# TLC5940Driver.net
KiCad netlist of a schematic drawn in EAGLE
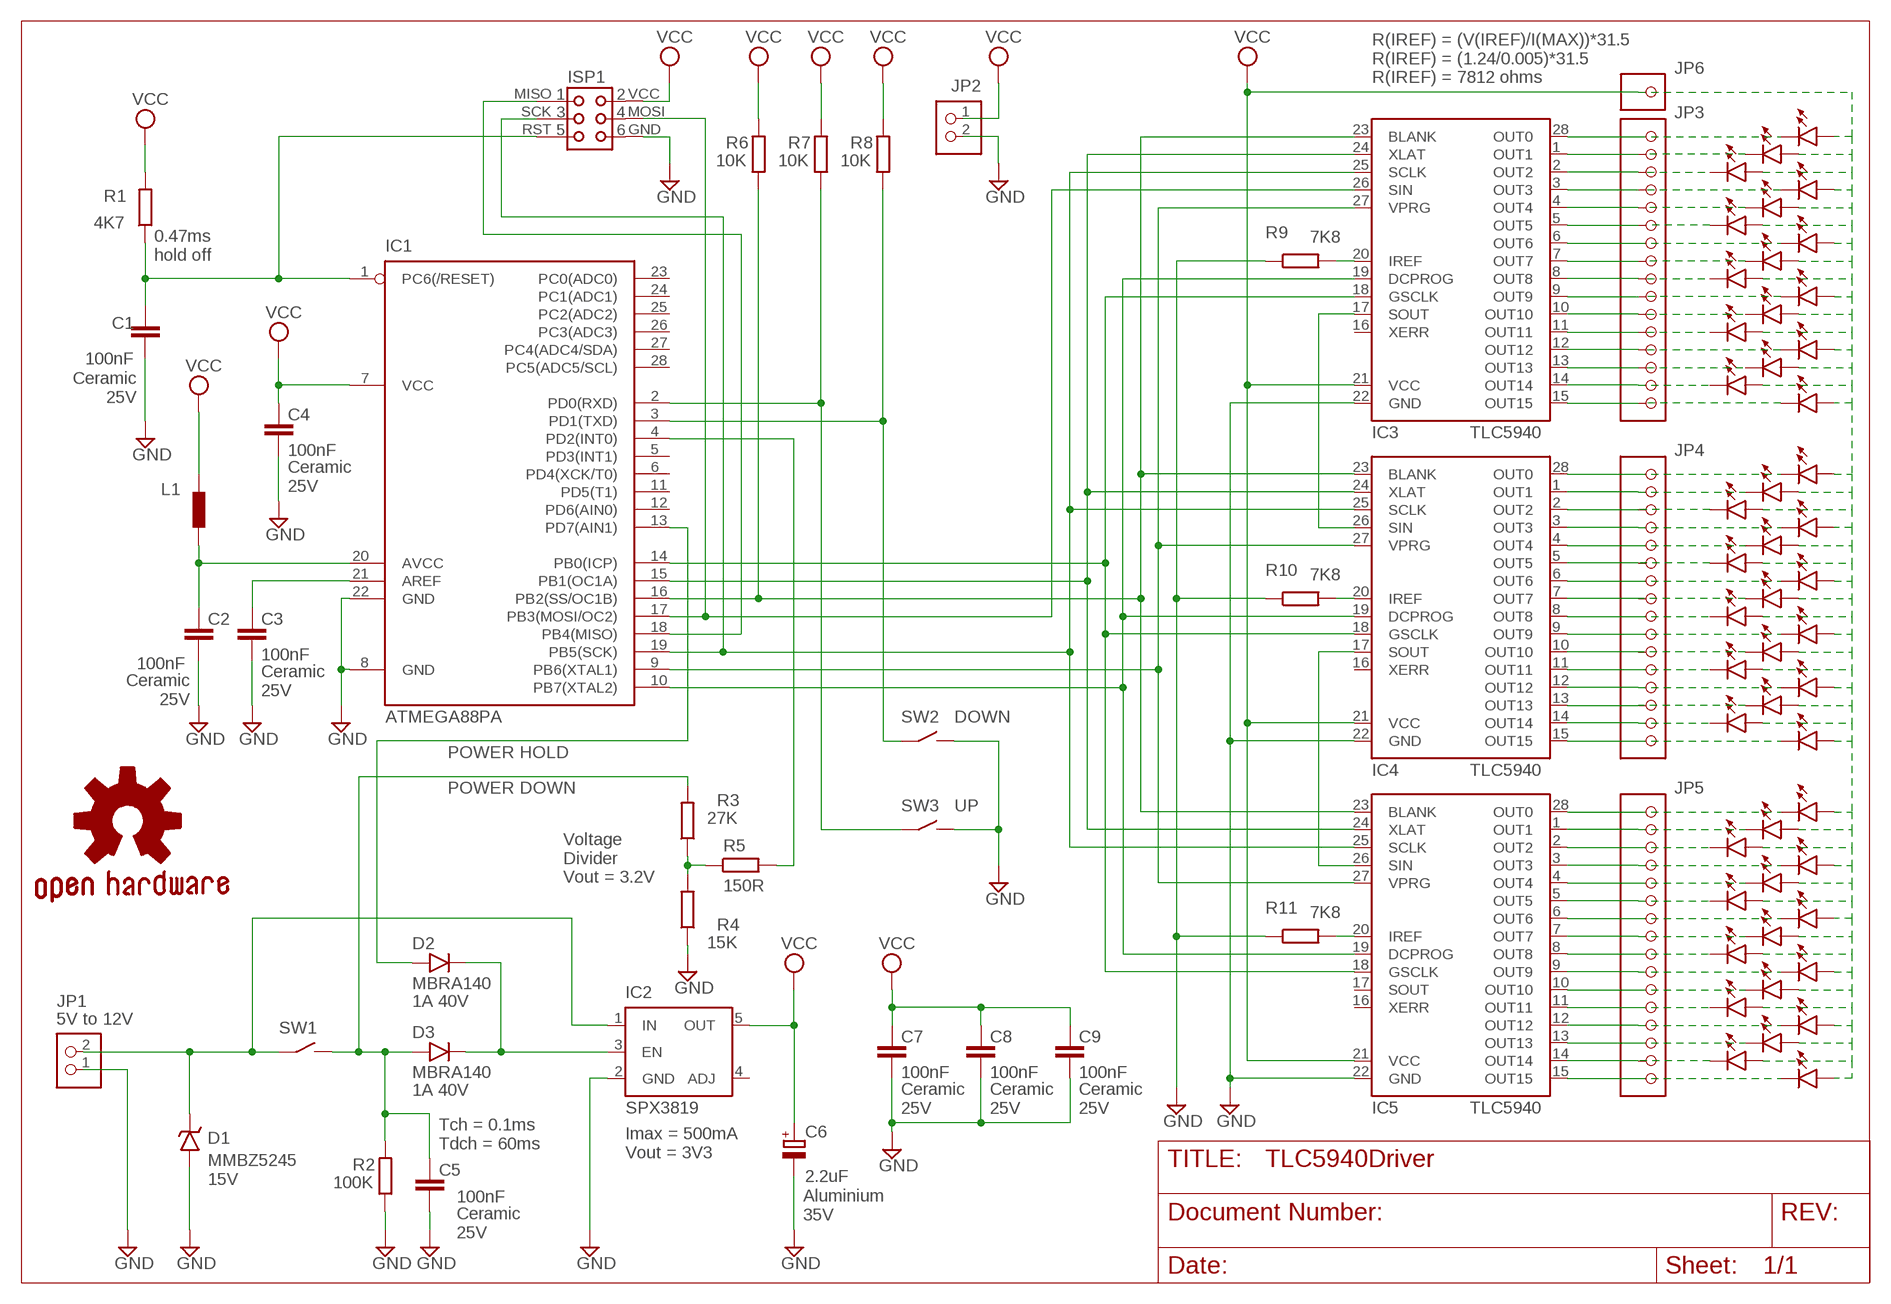
[diagram p0: schematic, sheet 1]

(export (version "E")
  (design (tool "Eeschema 10.0.6"))
  (components
    (comp (ref "C1")
      (value "100nF")
      (footprint "eagle-import:P-0805")
      (libsource (lib "eagle-import") (part "CAPACITOR"))
    )
    (comp (ref "C2")
      (value "100nF")
      (footprint "eagle-import:P-0805")
      (libsource (lib "eagle-import") (part "CAPACITOR"))
    )
    (comp (ref "C3")
      (value "100nF")
      (footprint "eagle-import:P-0805")
      (libsource (lib "eagle-import") (part "CAPACITOR"))
    )
    (comp (ref "C4")
      (value "100nF")
      (footprint "eagle-import:P-0805")
      (libsource (lib "eagle-import") (part "CAPACITOR"))
    )
    (comp (ref "C5")
      (value "100nF")
      (footprint "eagle-import:P-0805")
      (libsource (lib "eagle-import") (part "CAPACITOR"))
    )
    (comp (ref "C6")
      (value "2.2uF")
      (footprint "eagle-import:P-CAPNICHICON-3MM")
      (libsource (lib "eagle-import") (part "CAPACITOR-POL3"))
    )
    (comp (ref "C7")
      (value "100nF")
      (footprint "eagle-import:P-0805")
      (libsource (lib "eagle-import") (part "CAPACITOR"))
    )
    (comp (ref "C8")
      (value "100nF")
      (footprint "eagle-import:P-0805")
      (libsource (lib "eagle-import") (part "CAPACITOR"))
    )
    (comp (ref "C9")
      (value "100nF")
      (footprint "eagle-import:P-0805")
      (libsource (lib "eagle-import") (part "CAPACITOR"))
    )
    (comp (ref "D1")
      (value "ZENERS1")
      (footprint "eagle-import:P-SOT23-3")
      (libsource (lib "eagle-import") (part "ZENERS1"))
    )
    (comp (ref "D2")
      (value "MBRA140")
      (footprint "eagle-import:P-SMA")
      (libsource (lib "eagle-import") (part "DIODE"))
    )
    (comp (ref "D3")
      (value "MBRA140")
      (footprint "eagle-import:P-SMA")
      (libsource (lib "eagle-import") (part "DIODE"))
    )
    (comp (ref "GOLD_ORB_SM1")
      (value "OSHWLOGO_GOLD_ORB_SM")
      (footprint "eagle-import:OSHW2")
      (libsource (lib "eagle-import") (part "OSHWLOGO_GOLD_ORB_SM"))
    )
    (comp (ref "IC1")
      (value "ATMEGA88PA")
      (footprint "eagle-import:P-DIL28")
      (libsource (lib "eagle-import") (part "ATMEGA8/28PIN"))
    )
    (comp (ref "IC2")
      (value "SPX3819")
      (footprint "eagle-import:P-SOT23-5E")
      (libsource (lib "eagle-import") (part "VOLTAGE-REGULATOR-5PINEXTENDEDPADS"))
    )
    (comp (ref "IC3")
      (value "TLC5940")
      (footprint "eagle-import:P-DIL28")
      (libsource (lib "eagle-import") (part "TLC59401"))
    )
    (comp (ref "IC4")
      (value "TLC5940")
      (footprint "eagle-import:P-DIL28")
      (libsource (lib "eagle-import") (part "TLC59401"))
    )
    (comp (ref "IC5")
      (value "TLC5940")
      (footprint "eagle-import:P-DIL28")
      (libsource (lib "eagle-import") (part "TLC59401"))
    )
    (comp (ref "ISP1")
      (value "AVR-ISP-HEADERSHROUDED")
      (footprint "eagle-import:P-AVRISPSHROUDED")
      (libsource (lib "eagle-import") (part "AVR-ISP-HEADERSHROUDED"))
    )
    (comp (ref "JP1")
      (value "JST-XH-1X021")
      (footprint "eagle-import:P-JST-XH-1X02")
      (libsource (lib "eagle-import") (part "JST-XH-1X021"))
    )
    (comp (ref "JP2")
      (value "JST-XH-1X021")
      (footprint "eagle-import:P-JST-XH-1X02")
      (libsource (lib "eagle-import") (part "JST-XH-1X021"))
    )
    (comp (ref "JP3")
      (value "HEADER-1X16")
      (footprint "eagle-import:P-1X16")
      (libsource (lib "eagle-import") (part "HEADER-1X16"))
    )
    (comp (ref "JP4")
      (value "HEADER-1X16")
      (footprint "eagle-import:P-1X16")
      (libsource (lib "eagle-import") (part "HEADER-1X16"))
    )
    (comp (ref "JP5")
      (value "HEADER-1X16")
      (footprint "eagle-import:P-1X16")
      (libsource (lib "eagle-import") (part "HEADER-1X16"))
    )
    (comp (ref "JP6")
      (value "HEADER-1X01")
      (footprint "eagle-import:P-1X01")
      (libsource (lib "eagle-import") (part "HEADER-1X01"))
    )
    (comp (ref "L1")
      (value "INDUCTOR1")
      (footprint "eagle-import:P-0805")
      (libsource (lib "eagle-import") (part "INDUCTOR1"))
    )
    (comp (ref "LED1")
      (value "LED1")
      (footprint "eagle-import:P-PLCC2")
      (libsource (lib "eagle-import") (part "LED1"))
    )
    (comp (ref "LED2")
      (value "LED1")
      (footprint "eagle-import:P-PLCC2")
      (libsource (lib "eagle-import") (part "LED1"))
    )
    (comp (ref "LED3")
      (value "LED1")
      (footprint "eagle-import:P-PLCC2")
      (libsource (lib "eagle-import") (part "LED1"))
    )
    (comp (ref "LED4")
      (value "LED1")
      (footprint "eagle-import:P-PLCC2")
      (libsource (lib "eagle-import") (part "LED1"))
    )
    (comp (ref "LED5")
      (value "LED1")
      (footprint "eagle-import:P-PLCC2")
      (libsource (lib "eagle-import") (part "LED1"))
    )
    (comp (ref "LED6")
      (value "LED1")
      (footprint "eagle-import:P-PLCC2")
      (libsource (lib "eagle-import") (part "LED1"))
    )
    (comp (ref "LED7")
      (value "LED1")
      (footprint "eagle-import:P-PLCC2")
      (libsource (lib "eagle-import") (part "LED1"))
    )
    (comp (ref "LED8")
      (value "LED1")
      (footprint "eagle-import:P-PLCC2")
      (libsource (lib "eagle-import") (part "LED1"))
    )
    (comp (ref "LED9")
      (value "LED1")
      (footprint "eagle-import:P-PLCC2")
      (libsource (lib "eagle-import") (part "LED1"))
    )
    (comp (ref "LED10")
      (value "LED1")
      (footprint "eagle-import:P-PLCC2")
      (libsource (lib "eagle-import") (part "LED1"))
    )
    (comp (ref "LED11")
      (value "LED1")
      (footprint "eagle-import:P-PLCC2")
      (libsource (lib "eagle-import") (part "LED1"))
    )
    (comp (ref "LED12")
      (value "LED1")
      (footprint "eagle-import:P-PLCC2")
      (libsource (lib "eagle-import") (part "LED1"))
    )
    (comp (ref "LED13")
      (value "LED1")
      (footprint "eagle-import:P-PLCC2")
      (libsource (lib "eagle-import") (part "LED1"))
    )
    (comp (ref "LED14")
      (value "LED1")
      (footprint "eagle-import:P-PLCC2")
      (libsource (lib "eagle-import") (part "LED1"))
    )
    (comp (ref "LED15")
      (value "LED1")
      (footprint "eagle-import:P-PLCC2")
      (libsource (lib "eagle-import") (part "LED1"))
    )
    (comp (ref "LED16")
      (value "LED1")
      (footprint "eagle-import:P-PLCC2")
      (libsource (lib "eagle-import") (part "LED1"))
    )
    (comp (ref "LED17")
      (value "LED1")
      (footprint "eagle-import:P-PLCC2")
      (libsource (lib "eagle-import") (part "LED1"))
    )
    (comp (ref "LED18")
      (value "LED1")
      (footprint "eagle-import:P-PLCC2")
      (libsource (lib "eagle-import") (part "LED1"))
    )
    (comp (ref "LED19")
      (value "LED1")
      (footprint "eagle-import:P-PLCC2")
      (libsource (lib "eagle-import") (part "LED1"))
    )
    (comp (ref "LED20")
      (value "LED1")
      (footprint "eagle-import:P-PLCC2")
      (libsource (lib "eagle-import") (part "LED1"))
    )
    (comp (ref "LED21")
      (value "LED1")
      (footprint "eagle-import:P-PLCC2")
      (libsource (lib "eagle-import") (part "LED1"))
    )
    (comp (ref "LED22")
      (value "LED1")
      (footprint "eagle-import:P-PLCC2")
      (libsource (lib "eagle-import") (part "LED1"))
    )
    (comp (ref "LED23")
      (value "LED1")
      (footprint "eagle-import:P-PLCC2")
      (libsource (lib "eagle-import") (part "LED1"))
    )
    (comp (ref "LED24")
      (value "LED1")
      (footprint "eagle-import:P-PLCC2")
      (libsource (lib "eagle-import") (part "LED1"))
    )
    (comp (ref "LED25")
      (value "LED1")
      (footprint "eagle-import:P-PLCC2")
      (libsource (lib "eagle-import") (part "LED1"))
    )
    (comp (ref "LED26")
      (value "LED1")
      (footprint "eagle-import:P-PLCC2")
      (libsource (lib "eagle-import") (part "LED1"))
    )
    (comp (ref "LED27")
      (value "LED1")
      (footprint "eagle-import:P-PLCC2")
      (libsource (lib "eagle-import") (part "LED1"))
    )
    (comp (ref "LED28")
      (value "LED1")
      (footprint "eagle-import:P-PLCC2")
      (libsource (lib "eagle-import") (part "LED1"))
    )
    (comp (ref "LED29")
      (value "LED1")
      (footprint "eagle-import:P-PLCC2")
      (libsource (lib "eagle-import") (part "LED1"))
    )
    (comp (ref "LED30")
      (value "LED1")
      (footprint "eagle-import:P-PLCC2")
      (libsource (lib "eagle-import") (part "LED1"))
    )
    (comp (ref "LED31")
      (value "LED1")
      (footprint "eagle-import:P-PLCC2")
      (libsource (lib "eagle-import") (part "LED1"))
    )
    (comp (ref "LED32")
      (value "LED1")
      (footprint "eagle-import:P-PLCC2")
      (libsource (lib "eagle-import") (part "LED1"))
    )
    (comp (ref "LED33")
      (value "LED1")
      (footprint "eagle-import:P-PLCC2")
      (libsource (lib "eagle-import") (part "LED1"))
    )
    (comp (ref "LED34")
      (value "LED1")
      (footprint "eagle-import:P-PLCC2")
      (libsource (lib "eagle-import") (part "LED1"))
    )
    (comp (ref "LED35")
      (value "LED1")
      (footprint "eagle-import:P-PLCC2")
      (libsource (lib "eagle-import") (part "LED1"))
    )
    (comp (ref "LED36")
      (value "LED1")
      (footprint "eagle-import:P-PLCC2")
      (libsource (lib "eagle-import") (part "LED1"))
    )
    (comp (ref "LED37")
      (value "LED1")
      (footprint "eagle-import:P-PLCC2")
      (libsource (lib "eagle-import") (part "LED1"))
    )
    (comp (ref "LED38")
      (value "LED1")
      (footprint "eagle-import:P-PLCC2")
      (libsource (lib "eagle-import") (part "LED1"))
    )
    (comp (ref "LED39")
      (value "LED1")
      (footprint "eagle-import:P-PLCC2")
      (libsource (lib "eagle-import") (part "LED1"))
    )
    (comp (ref "LED40")
      (value "LED1")
      (footprint "eagle-import:P-PLCC2")
      (libsource (lib "eagle-import") (part "LED1"))
    )
    (comp (ref "LED41")
      (value "LED1")
      (footprint "eagle-import:P-PLCC2")
      (libsource (lib "eagle-import") (part "LED1"))
    )
    (comp (ref "LED42")
      (value "LED1")
      (footprint "eagle-import:P-PLCC2")
      (libsource (lib "eagle-import") (part "LED1"))
    )
    (comp (ref "LED43")
      (value "LED1")
      (footprint "eagle-import:P-PLCC2")
      (libsource (lib "eagle-import") (part "LED1"))
    )
    (comp (ref "LED44")
      (value "LED1")
      (footprint "eagle-import:P-PLCC2")
      (libsource (lib "eagle-import") (part "LED1"))
    )
    (comp (ref "LED45")
      (value "LED1")
      (footprint "eagle-import:P-PLCC2")
      (libsource (lib "eagle-import") (part "LED1"))
    )
    (comp (ref "LED46")
      (value "LED1")
      (footprint "eagle-import:P-PLCC2")
      (libsource (lib "eagle-import") (part "LED1"))
    )
    (comp (ref "LED47")
      (value "LED1")
      (footprint "eagle-import:P-PLCC2")
      (libsource (lib "eagle-import") (part "LED1"))
    )
    (comp (ref "LED48")
      (value "LED1")
      (footprint "eagle-import:P-PLCC2")
      (libsource (lib "eagle-import") (part "LED1"))
    )
    (comp (ref "R1")
      (value "4K7")
      (footprint "eagle-import:P-0805")
      (libsource (lib "eagle-import") (part "RESISTOR{dblquote}{dblquote}"))
    )
    (comp (ref "R2")
      (value "100K")
      (footprint "eagle-import:P-0805")
      (libsource (lib "eagle-import") (part "RESISTOR{dblquote}{dblquote}"))
    )
    (comp (ref "R3")
      (value "27K")
      (footprint "eagle-import:P-0805")
      (libsource (lib "eagle-import") (part "RESISTOR{dblquote}{dblquote}"))
    )
    (comp (ref "R4")
      (value "15K")
      (footprint "eagle-import:P-0805")
      (libsource (lib "eagle-import") (part "RESISTOR{dblquote}{dblquote}"))
    )
    (comp (ref "R5")
      (value "150R")
      (footprint "eagle-import:P-0805")
      (libsource (lib "eagle-import") (part "RESISTOR{dblquote}{dblquote}"))
    )
    (comp (ref "R6")
      (value "10K")
      (footprint "eagle-import:P-0805")
      (libsource (lib "eagle-import") (part "RESISTOR{dblquote}{dblquote}"))
    )
    (comp (ref "R7")
      (value "10K")
      (footprint "eagle-import:P-0805")
      (libsource (lib "eagle-import") (part "RESISTOR{dblquote}{dblquote}"))
    )
    (comp (ref "R8")
      (value "10K")
      (footprint "eagle-import:P-0805")
      (libsource (lib "eagle-import") (part "RESISTOR{dblquote}{dblquote}"))
    )
    (comp (ref "R9")
      (value "7K8")
      (footprint "eagle-import:P-0805")
      (libsource (lib "eagle-import") (part "RESISTOR{dblquote}{dblquote}"))
    )
    (comp (ref "R10")
      (value "7K8")
      (footprint "eagle-import:P-0805")
      (libsource (lib "eagle-import") (part "RESISTOR{dblquote}{dblquote}"))
    )
    (comp (ref "R11")
      (value "7K8")
      (footprint "eagle-import:P-0805")
      (libsource (lib "eagle-import") (part "RESISTOR{dblquote}{dblquote}"))
    )
    (comp (ref "SW1")
      (value "SWITCH-2PIN4")
      (footprint "eagle-import:P-JST-XH-1X02-VERT")
      (libsource (lib "eagle-import") (part "SWITCH-2PIN4"))
    )
    (comp (ref "SW2")
      (value "SWITCH-2PIN4")
      (footprint "eagle-import:P-JST-XH-1X02-VERT")
      (libsource (lib "eagle-import") (part "SWITCH-2PIN4"))
    )
    (comp (ref "SW3")
      (value "SWITCH-2PIN4")
      (footprint "eagle-import:P-JST-XH-1X02-VERT")
      (libsource (lib "eagle-import") (part "SWITCH-2PIN4"))
    )
  )
  (nets
    (net (code "1") (name "GND") (class "Default")
      (node (ref "C1") (pin "2") (pinfunction "2_2") (pintype "passive"))
      (node (ref "C2") (pin "2") (pinfunction "2_2") (pintype "passive"))
      (node (ref "C3") (pin "2") (pinfunction "2_2") (pintype "passive"))
      (node (ref "C4") (pin "2") (pinfunction "2_2") (pintype "passive"))
      (node (ref "C5") (pin "2") (pinfunction "2_2") (pintype "passive"))
      (node (ref "C6") (pin "2") (pinfunction "-_2") (pintype "passive"))
      (node (ref "C7") (pin "2") (pinfunction "2_2") (pintype "passive"))
      (node (ref "C8") (pin "2") (pinfunction "2_2") (pintype "passive"))
      (node (ref "C9") (pin "2") (pinfunction "2_2") (pintype "passive"))
      (node (ref "D1") (pin "1") (pinfunction "A_1") (pintype "passive"))
      (node (ref "IC1") (pin "22") (pinfunction "GND_22") (pintype "power_in"))
      (node (ref "IC1") (pin "8") (pinfunction "GND_8") (pintype "power_in"))
      (node (ref "IC2") (pin "2") (pinfunction "GND_2") (pintype "power_in"))
      (node (ref "IC3") (pin "22") (pinfunction "GND_22") (pintype "power_in"))
      (node (ref "IC4") (pin "22") (pinfunction "GND_22") (pintype "power_in"))
      (node (ref "IC5") (pin "22") (pinfunction "GND_22") (pintype "power_in"))
      (node (ref "ISP1") (pin "GND") (pinfunction "GND_GND") (pintype "power_in"))
      (node (ref "JP1") (pin "1") (pinfunction "1_1") (pintype "bidirectional"))
      (node (ref "JP2") (pin "2") (pinfunction "2_2") (pintype "bidirectional"))
      (node (ref "R10") (pin "1") (pinfunction "1_1") (pintype "passive"))
      (node (ref "R11") (pin "1") (pinfunction "1_1") (pintype "passive"))
      (node (ref "R2") (pin "1") (pinfunction "1_1") (pintype "passive"))
      (node (ref "R4") (pin "1") (pinfunction "1_1") (pintype "passive"))
      (node (ref "R9") (pin "1") (pinfunction "1_1") (pintype "passive"))
      (node (ref "SW2") (pin "2") (pinfunction "P$2_2") (pintype "bidirectional"))
      (node (ref "SW3") (pin "2") (pinfunction "P$2_2") (pintype "bidirectional"))
    )
    (net (code "2") (name "Net-(D1-C)") (class "Default")
      (node (ref "D1") (pin "3") (pinfunction "C_3") (pintype "passive"))
      (node (ref "IC2") (pin "1") (pinfunction "IN_1") (pintype "input"))
      (node (ref "JP1") (pin "2") (pinfunction "2_2") (pintype "bidirectional"))
      (node (ref "SW1") (pin "1") (pinfunction "P$1_1") (pintype "bidirectional"))
    )
    (net (code "3") (name "Net-(D2-C)") (class "Default")
      (node (ref "D2") (pin "K") (pinfunction "C_K") (pintype "passive"))
      (node (ref "D3") (pin "K") (pinfunction "C_K") (pintype "passive"))
      (node (ref "IC2") (pin "3") (pinfunction "EN_3") (pintype "input"))
    )
    (net (code "4") (name "Net-(IC1-AREF)") (class "Default")
      (node (ref "C3") (pin "1") (pinfunction "1_1") (pintype "passive"))
      (node (ref "IC1") (pin "21") (pinfunction "AREF_21") (pintype "passive"))
    )
    (net (code "5") (name "Net-(IC1-AVCC)") (class "Default")
      (node (ref "C2") (pin "1") (pinfunction "1_1") (pintype "passive"))
      (node (ref "IC1") (pin "20") (pinfunction "AVCC_20") (pintype "power_in"))
      (node (ref "L1") (pin "1") (pinfunction "1_1") (pintype "passive"))
    )
    (net (code "6") (name "Net-(IC1-PB0(ICP))") (class "Default")
      (node (ref "IC1") (pin "14") (pinfunction "PB0(ICP)_14") (pintype "bidirectional"))
      (node (ref "IC3") (pin "18") (pinfunction "GSCLK_18") (pintype "input"))
      (node (ref "IC4") (pin "18") (pinfunction "GSCLK_18") (pintype "input"))
      (node (ref "IC5") (pin "18") (pinfunction "GSCLK_18") (pintype "input"))
    )
    (net (code "7") (name "Net-(IC1-PB1(OC1A))") (class "Default")
      (node (ref "IC1") (pin "15") (pinfunction "PB1(OC1A)_15") (pintype "bidirectional"))
      (node (ref "IC3") (pin "24") (pinfunction "XLAT_24") (pintype "input"))
      (node (ref "IC4") (pin "24") (pinfunction "XLAT_24") (pintype "input"))
      (node (ref "IC5") (pin "24") (pinfunction "XLAT_24") (pintype "input"))
    )
    (net (code "8") (name "Net-(IC1-PB2(SS{slash}OC1B))") (class "Default")
      (node (ref "IC1") (pin "16") (pinfunction "PB2(SS/OC1B)_16") (pintype "bidirectional"))
      (node (ref "IC3") (pin "23") (pinfunction "BLANK_23") (pintype "input"))
      (node (ref "IC4") (pin "23") (pinfunction "BLANK_23") (pintype "input"))
      (node (ref "IC5") (pin "23") (pinfunction "BLANK_23") (pintype "input"))
      (node (ref "R6") (pin "1") (pinfunction "1_1") (pintype "passive"))
    )
    (net (code "9") (name "Net-(IC1-PB3(MOSI{slash}OC2))") (class "Default")
      (node (ref "IC1") (pin "17") (pinfunction "PB3(MOSI/OC2)_17") (pintype "bidirectional"))
      (node (ref "IC3") (pin "26") (pinfunction "SIN_26") (pintype "input"))
      (node (ref "ISP1") (pin "MOSI") (pinfunction "MOSI_MOSI") (pintype "bidirectional"))
    )
    (net (code "10") (name "Net-(IC1-PB4(MISO))") (class "Default")
      (node (ref "IC1") (pin "18") (pinfunction "PB4(MISO)_18") (pintype "bidirectional"))
      (node (ref "ISP1") (pin "MISO") (pinfunction "MISO_MISO") (pintype "bidirectional"))
    )
    (net (code "11") (name "Net-(IC1-PB5(SCK))") (class "Default")
      (node (ref "IC1") (pin "19") (pinfunction "PB5(SCK)_19") (pintype "bidirectional"))
      (node (ref "IC3") (pin "25") (pinfunction "SCLK_25") (pintype "input"))
      (node (ref "IC4") (pin "25") (pinfunction "SCLK_25") (pintype "input"))
      (node (ref "IC5") (pin "25") (pinfunction "SCLK_25") (pintype "input"))
      (node (ref "ISP1") (pin "SCK") (pinfunction "SCK_SCK") (pintype "bidirectional"))
    )
    (net (code "12") (name "Net-(IC1-PB6(XTAL1))") (class "Default")
      (node (ref "IC1") (pin "9") (pinfunction "PB6(XTAL1)_9") (pintype "bidirectional"))
      (node (ref "IC3") (pin "27") (pinfunction "VPRG_27") (pintype "input"))
      (node (ref "IC4") (pin "27") (pinfunction "VPRG_27") (pintype "input"))
      (node (ref "IC5") (pin "27") (pinfunction "VPRG_27") (pintype "input"))
    )
    (net (code "13") (name "Net-(IC1-PB7(XTAL2))") (class "Default")
      (node (ref "IC1") (pin "10") (pinfunction "PB7(XTAL2)_10") (pintype "bidirectional"))
      (node (ref "IC3") (pin "19") (pinfunction "DCPROG_19") (pintype "input"))
      (node (ref "IC4") (pin "19") (pinfunction "DCPROG_19") (pintype "input"))
      (node (ref "IC5") (pin "19") (pinfunction "DCPROG_19") (pintype "input"))
    )
    (net (code "14") (name "Net-(IC1-PC6({slash}RESET))") (class "Default")
      (node (ref "C1") (pin "1") (pinfunction "1_1") (pintype "passive"))
      (node (ref "IC1") (pin "1") (pinfunction "PC6(/RESET)_1") (pintype "bidirectional"))
      (node (ref "ISP1") (pin "RST") (pinfunction "RST_RST") (pintype "bidirectional"))
      (node (ref "R1") (pin "1") (pinfunction "1_1") (pintype "passive"))
    )
    (net (code "15") (name "Net-(IC1-PD0(RXD))") (class "Default")
      (node (ref "IC1") (pin "2") (pinfunction "PD0(RXD)_2") (pintype "bidirectional"))
      (node (ref "R7") (pin "1") (pinfunction "1_1") (pintype "passive"))
      (node (ref "SW3") (pin "1") (pinfunction "P$1_1") (pintype "bidirectional"))
    )
    (net (code "16") (name "Net-(IC1-PD1(TXD))") (class "Default")
      (node (ref "IC1") (pin "3") (pinfunction "PD1(TXD)_3") (pintype "bidirectional"))
      (node (ref "R8") (pin "1") (pinfunction "1_1") (pintype "passive"))
      (node (ref "SW2") (pin "1") (pinfunction "P$1_1") (pintype "bidirectional"))
    )
    (net (code "17") (name "Net-(IC1-PD2(INT0))") (class "Default")
      (node (ref "IC1") (pin "4") (pinfunction "PD2(INT0)_4") (pintype "bidirectional"))
      (node (ref "R5") (pin "2") (pinfunction "2_2") (pintype "passive"))
    )
    (net (code "18") (name "Net-(IC1-PD7(AIN1))") (class "Default")
      (node (ref "D2") (pin "A") (pinfunction "A_A") (pintype "passive"))
      (node (ref "IC1") (pin "13") (pinfunction "PD7(AIN1)_13") (pintype "bidirectional"))
    )
    (net (code "19") (name "Net-(IC3-IREF)") (class "Default")
      (node (ref "IC3") (pin "20") (pinfunction "IREF_20") (pintype "input"))
      (node (ref "R9") (pin "2") (pinfunction "2_2") (pintype "passive"))
    )
    (net (code "20") (name "Net-(IC3-OUT0)") (class "Default")
      (node (ref "IC3") (pin "28") (pinfunction "OUT0_28") (pintype "output"))
      (node (ref "JP3") (pin "1") (pinfunction "P$1_1") (pintype "bidirectional"))
      (node (ref "LED1") (pin "C") (pinfunction "C_C") (pintype "passive"))
    )
    (net (code "21") (name "Net-(IC3-OUT1)") (class "Default")
      (node (ref "IC3") (pin "1") (pinfunction "OUT1_1") (pintype "output"))
      (node (ref "JP3") (pin "2") (pinfunction "P$2_2") (pintype "bidirectional"))
    )
    (net (code "22") (name "Net-(IC3-OUT2)") (class "Default")
      (node (ref "IC3") (pin "2") (pinfunction "OUT2_2") (pintype "output"))
      (node (ref "JP3") (pin "3") (pinfunction "P$3_3") (pintype "bidirectional"))
    )
    (net (code "23") (name "Net-(IC3-OUT3)") (class "Default")
      (node (ref "IC3") (pin "3") (pinfunction "OUT3_3") (pintype "output"))
      (node (ref "JP3") (pin "4") (pinfunction "P$4_4") (pintype "bidirectional"))
    )
    (net (code "24") (name "Net-(IC3-OUT4)") (class "Default")
      (node (ref "IC3") (pin "4") (pinfunction "OUT4_4") (pintype "output"))
      (node (ref "JP3") (pin "5") (pinfunction "P$5_5") (pintype "bidirectional"))
    )
    (net (code "25") (name "Net-(IC3-OUT5)") (class "Default")
      (node (ref "IC3") (pin "5") (pinfunction "OUT5_5") (pintype "output"))
      (node (ref "JP3") (pin "6") (pinfunction "P$6_6") (pintype "bidirectional"))
    )
    (net (code "26") (name "Net-(IC3-OUT6)") (class "Default")
      (node (ref "IC3") (pin "6") (pinfunction "OUT6_6") (pintype "output"))
      (node (ref "JP3") (pin "7") (pinfunction "P$7_7") (pintype "bidirectional"))
      (node (ref "LED7") (pin "C") (pinfunction "C_C") (pintype "passive"))
    )
    (net (code "27") (name "Net-(IC3-OUT7)") (class "Default")
      (node (ref "IC3") (pin "7") (pinfunction "OUT7_7") (pintype "output"))
      (node (ref "JP3") (pin "8") (pinfunction "P$8_8") (pintype "bidirectional"))
    )
    (net (code "28") (name "Net-(IC3-OUT8)") (class "Default")
      (node (ref "IC3") (pin "8") (pinfunction "OUT8_8") (pintype "output"))
      (node (ref "JP3") (pin "9") (pinfunction "P$9_9") (pintype "bidirectional"))
    )
    (net (code "29") (name "Net-(IC3-OUT9)") (class "Default")
      (node (ref "IC3") (pin "9") (pinfunction "OUT9_9") (pintype "output"))
      (node (ref "JP3") (pin "10") (pinfunction "P$10_10") (pintype "bidirectional"))
    )
    (net (code "30") (name "Net-(IC3-OUT10)") (class "Default")
      (node (ref "IC3") (pin "10") (pinfunction "OUT10_10") (pintype "output"))
      (node (ref "JP3") (pin "11") (pinfunction "P$11_11") (pintype "bidirectional"))
    )
    (net (code "31") (name "Net-(IC3-OUT11)") (class "Default")
      (node (ref "IC3") (pin "11") (pinfunction "OUT11_11") (pintype "output"))
      (node (ref "JP3") (pin "12") (pinfunction "P$12_12") (pintype "bidirectional"))
    )
    (net (code "32") (name "Net-(IC3-OUT12)") (class "Default")
      (node (ref "IC3") (pin "12") (pinfunction "OUT12_12") (pintype "output"))
      (node (ref "JP3") (pin "13") (pinfunction "P$13_13") (pintype "bidirectional"))
    )
    (net (code "33") (name "Net-(IC3-OUT13)") (class "Default")
      (node (ref "IC3") (pin "13") (pinfunction "OUT13_13") (pintype "output"))
      (node (ref "JP3") (pin "14") (pinfunction "P$14_14") (pintype "bidirectional"))
    )
    (net (code "34") (name "Net-(IC3-OUT14)") (class "Default")
      (node (ref "IC3") (pin "14") (pinfunction "OUT14_14") (pintype "output"))
      (node (ref "JP3") (pin "15") (pinfunction "P$15_15") (pintype "bidirectional"))
      (node (ref "LED15") (pin "C") (pinfunction "C_C") (pintype "passive"))
    )
    (net (code "35") (name "Net-(IC3-OUT15)") (class "Default")
      (node (ref "IC3") (pin "15") (pinfunction "OUT15_15") (pintype "output"))
      (node (ref "JP3") (pin "16") (pinfunction "P$16_16") (pintype "bidirectional"))
    )
    (net (code "36") (name "Net-(IC3-SOUT)") (class "Default")
      (node (ref "IC3") (pin "17") (pinfunction "SOUT_17") (pintype "output"))
      (node (ref "IC4") (pin "26") (pinfunction "SIN_26") (pintype "input"))
    )
    (net (code "37") (name "Net-(IC4-IREF)") (class "Default")
      (node (ref "IC4") (pin "20") (pinfunction "IREF_20") (pintype "input"))
      (node (ref "R10") (pin "2") (pinfunction "2_2") (pintype "passive"))
    )
    (net (code "38") (name "Net-(IC4-OUT0)") (class "Default")
      (node (ref "IC4") (pin "28") (pinfunction "OUT0_28") (pintype "output"))
      (node (ref "JP4") (pin "1") (pinfunction "P$1_1") (pintype "bidirectional"))
      (node (ref "LED17") (pin "C") (pinfunction "C_C") (pintype "passive"))
    )
    (net (code "39") (name "Net-(IC4-OUT1)") (class "Default")
      (node (ref "IC4") (pin "1") (pinfunction "OUT1_1") (pintype "output"))
      (node (ref "JP4") (pin "2") (pinfunction "P$2_2") (pintype "bidirectional"))
      (node (ref "LED18") (pin "C") (pinfunction "C_C") (pintype "passive"))
    )
    (net (code "40") (name "Net-(IC4-OUT2)") (class "Default")
      (node (ref "IC4") (pin "2") (pinfunction "OUT2_2") (pintype "output"))
      (node (ref "JP4") (pin "3") (pinfunction "P$3_3") (pintype "bidirectional"))
      (node (ref "LED19") (pin "C") (pinfunction "C_C") (pintype "passive"))
    )
    (net (code "41") (name "Net-(IC4-OUT3)") (class "Default")
      (node (ref "IC4") (pin "3") (pinfunction "OUT3_3") (pintype "output"))
      (node (ref "JP4") (pin "4") (pinfunction "P$4_4") (pintype "bidirectional"))
      (node (ref "LED20") (pin "C") (pinfunction "C_C") (pintype "passive"))
    )
    (net (code "42") (name "Net-(IC4-OUT4)") (class "Default")
      (node (ref "IC4") (pin "4") (pinfunction "OUT4_4") (pintype "output"))
      (node (ref "JP4") (pin "5") (pinfunction "P$5_5") (pintype "bidirectional"))
      (node (ref "LED21") (pin "C") (pinfunction "C_C") (pintype "passive"))
    )
    (net (code "43") (name "Net-(IC4-OUT5)") (class "Default")
      (node (ref "IC4") (pin "5") (pinfunction "OUT5_5") (pintype "output"))
      (node (ref "JP4") (pin "6") (pinfunction "P$6_6") (pintype "bidirectional"))
      (node (ref "LED22") (pin "C") (pinfunction "C_C") (pintype "passive"))
    )
    (net (code "44") (name "Net-(IC4-OUT6)") (class "Default")
      (node (ref "IC4") (pin "6") (pinfunction "OUT6_6") (pintype "output"))
      (node (ref "JP4") (pin "7") (pinfunction "P$7_7") (pintype "bidirectional"))
      (node (ref "LED23") (pin "C") (pinfunction "C_C") (pintype "passive"))
    )
    (net (code "45") (name "Net-(IC4-OUT7)") (class "Default")
      (node (ref "IC4") (pin "7") (pinfunction "OUT7_7") (pintype "output"))
      (node (ref "JP4") (pin "8") (pinfunction "P$8_8") (pintype "bidirectional"))
      (node (ref "LED24") (pin "C") (pinfunction "C_C") (pintype "passive"))
    )
    (net (code "46") (name "Net-(IC4-OUT8)") (class "Default")
      (node (ref "IC4") (pin "8") (pinfunction "OUT8_8") (pintype "output"))
      (node (ref "JP4") (pin "9") (pinfunction "P$9_9") (pintype "bidirectional"))
      (node (ref "LED25") (pin "C") (pinfunction "C_C") (pintype "passive"))
    )
    (net (code "47") (name "Net-(IC4-OUT9)") (class "Default")
      (node (ref "IC4") (pin "9") (pinfunction "OUT9_9") (pintype "output"))
      (node (ref "JP4") (pin "10") (pinfunction "P$10_10") (pintype "bidirectional"))
      (node (ref "LED26") (pin "C") (pinfunction "C_C") (pintype "passive"))
    )
    (net (code "48") (name "Net-(IC4-OUT10)") (class "Default")
      (node (ref "IC4") (pin "10") (pinfunction "OUT10_10") (pintype "output"))
      (node (ref "JP4") (pin "11") (pinfunction "P$11_11") (pintype "bidirectional"))
      (node (ref "LED27") (pin "C") (pinfunction "C_C") (pintype "passive"))
    )
    (net (code "49") (name "Net-(IC4-OUT11)") (class "Default")
      (node (ref "IC4") (pin "11") (pinfunction "OUT11_11") (pintype "output"))
      (node (ref "JP4") (pin "12") (pinfunction "P$12_12") (pintype "bidirectional"))
      (node (ref "LED28") (pin "C") (pinfunction "C_C") (pintype "passive"))
    )
    (net (code "50") (name "Net-(IC4-OUT12)") (class "Default")
      (node (ref "IC4") (pin "12") (pinfunction "OUT12_12") (pintype "output"))
      (node (ref "JP4") (pin "13") (pinfunction "P$13_13") (pintype "bidirectional"))
      (node (ref "LED29") (pin "C") (pinfunction "C_C") (pintype "passive"))
    )
    (net (code "51") (name "Net-(IC4-OUT13)") (class "Default")
      (node (ref "IC4") (pin "13") (pinfunction "OUT13_13") (pintype "output"))
      (node (ref "JP4") (pin "14") (pinfunction "P$14_14") (pintype "bidirectional"))
      (node (ref "LED30") (pin "C") (pinfunction "C_C") (pintype "passive"))
    )
    (net (code "52") (name "Net-(IC4-OUT14)") (class "Default")
      (node (ref "IC4") (pin "14") (pinfunction "OUT14_14") (pintype "output"))
      (node (ref "JP4") (pin "15") (pinfunction "P$15_15") (pintype "bidirectional"))
      (node (ref "LED31") (pin "C") (pinfunction "C_C") (pintype "passive"))
    )
    (net (code "53") (name "Net-(IC4-OUT15)") (class "Default")
      (node (ref "IC4") (pin "15") (pinfunction "OUT15_15") (pintype "output"))
      (node (ref "JP4") (pin "16") (pinfunction "P$16_16") (pintype "bidirectional"))
      (node (ref "LED32") (pin "C") (pinfunction "C_C") (pintype "passive"))
    )
    (net (code "54") (name "Net-(IC4-SOUT)") (class "Default")
      (node (ref "IC4") (pin "17") (pinfunction "SOUT_17") (pintype "output"))
      (node (ref "IC5") (pin "26") (pinfunction "SIN_26") (pintype "input"))
    )
    (net (code "55") (name "Net-(IC5-IREF)") (class "Default")
      (node (ref "IC5") (pin "20") (pinfunction "IREF_20") (pintype "input"))
      (node (ref "R11") (pin "2") (pinfunction "2_2") (pintype "passive"))
    )
    (net (code "56") (name "Net-(IC5-OUT0)") (class "Default")
      (node (ref "IC5") (pin "28") (pinfunction "OUT0_28") (pintype "output"))
      (node (ref "JP5") (pin "1") (pinfunction "P$1_1") (pintype "bidirectional"))
      (node (ref "LED33") (pin "C") (pinfunction "C_C") (pintype "passive"))
    )
    (net (code "57") (name "Net-(IC5-OUT1)") (class "Default")
      (node (ref "IC5") (pin "1") (pinfunction "OUT1_1") (pintype "output"))
      (node (ref "JP5") (pin "2") (pinfunction "P$2_2") (pintype "bidirectional"))
      (node (ref "LED34") (pin "C") (pinfunction "C_C") (pintype "passive"))
    )
    (net (code "58") (name "Net-(IC5-OUT2)") (class "Default")
      (node (ref "IC5") (pin "2") (pinfunction "OUT2_2") (pintype "output"))
      (node (ref "JP5") (pin "3") (pinfunction "P$3_3") (pintype "bidirectional"))
      (node (ref "LED35") (pin "C") (pinfunction "C_C") (pintype "passive"))
    )
    (net (code "59") (name "Net-(IC5-OUT3)") (class "Default")
      (node (ref "IC5") (pin "3") (pinfunction "OUT3_3") (pintype "output"))
      (node (ref "JP5") (pin "4") (pinfunction "P$4_4") (pintype "bidirectional"))
      (node (ref "LED36") (pin "C") (pinfunction "C_C") (pintype "passive"))
    )
    (net (code "60") (name "Net-(IC5-OUT4)") (class "Default")
      (node (ref "IC5") (pin "4") (pinfunction "OUT4_4") (pintype "output"))
      (node (ref "JP5") (pin "5") (pinfunction "P$5_5") (pintype "bidirectional"))
      (node (ref "LED37") (pin "C") (pinfunction "C_C") (pintype "passive"))
    )
    (net (code "61") (name "Net-(IC5-OUT5)") (class "Default")
      (node (ref "IC5") (pin "5") (pinfunction "OUT5_5") (pintype "output"))
      (node (ref "JP5") (pin "6") (pinfunction "P$6_6") (pintype "bidirectional"))
      (node (ref "LED38") (pin "C") (pinfunction "C_C") (pintype "passive"))
    )
    (net (code "62") (name "Net-(IC5-OUT6)") (class "Default")
      (node (ref "IC5") (pin "6") (pinfunction "OUT6_6") (pintype "output"))
      (node (ref "JP5") (pin "7") (pinfunction "P$7_7") (pintype "bidirectional"))
      (node (ref "LED39") (pin "C") (pinfunction "C_C") (pintype "passive"))
    )
    (net (code "63") (name "Net-(IC5-OUT7)") (class "Default")
      (node (ref "IC5") (pin "7") (pinfunction "OUT7_7") (pintype "output"))
      (node (ref "JP5") (pin "8") (pinfunction "P$8_8") (pintype "bidirectional"))
      (node (ref "LED40") (pin "C") (pinfunction "C_C") (pintype "passive"))
    )
    (net (code "64") (name "Net-(IC5-OUT8)") (class "Default")
      (node (ref "IC5") (pin "8") (pinfunction "OUT8_8") (pintype "output"))
      (node (ref "JP5") (pin "9") (pinfunction "P$9_9") (pintype "bidirectional"))
      (node (ref "LED41") (pin "C") (pinfunction "C_C") (pintype "passive"))
    )
    (net (code "65") (name "Net-(IC5-OUT9)") (class "Default")
      (node (ref "IC5") (pin "9") (pinfunction "OUT9_9") (pintype "output"))
      (node (ref "JP5") (pin "10") (pinfunction "P$10_10") (pintype "bidirectional"))
      (node (ref "LED42") (pin "C") (pinfunction "C_C") (pintype "passive"))
    )
    (net (code "66") (name "Net-(IC5-OUT10)") (class "Default")
      (node (ref "IC5") (pin "10") (pinfunction "OUT10_10") (pintype "output"))
      (node (ref "JP5") (pin "11") (pinfunction "P$11_11") (pintype "bidirectional"))
      (node (ref "LED43") (pin "C") (pinfunction "C_C") (pintype "passive"))
    )
    (net (code "67") (name "Net-(IC5-OUT11)") (class "Default")
      (node (ref "IC5") (pin "11") (pinfunction "OUT11_11") (pintype "output"))
      (node (ref "JP5") (pin "12") (pinfunction "P$12_12") (pintype "bidirectional"))
      (node (ref "LED44") (pin "C") (pinfunction "C_C") (pintype "passive"))
    )
    (net (code "68") (name "Net-(IC5-OUT12)") (class "Default")
      (node (ref "IC5") (pin "12") (pinfunction "OUT12_12") (pintype "output"))
      (node (ref "JP5") (pin "13") (pinfunction "P$13_13") (pintype "bidirectional"))
      (node (ref "LED45") (pin "C") (pinfunction "C_C") (pintype "passive"))
    )
    (net (code "69") (name "Net-(IC5-OUT13)") (class "Default")
      (node (ref "IC5") (pin "13") (pinfunction "OUT13_13") (pintype "output"))
      (node (ref "JP5") (pin "14") (pinfunction "P$14_14") (pintype "bidirectional"))
      (node (ref "LED46") (pin "C") (pinfunction "C_C") (pintype "passive"))
    )
    (net (code "70") (name "Net-(IC5-OUT14)") (class "Default")
      (node (ref "IC5") (pin "14") (pinfunction "OUT14_14") (pintype "output"))
      (node (ref "JP5") (pin "15") (pinfunction "P$15_15") (pintype "bidirectional"))
      (node (ref "LED47") (pin "C") (pinfunction "C_C") (pintype "passive"))
    )
    (net (code "71") (name "Net-(IC5-OUT15)") (class "Default")
      (node (ref "IC5") (pin "15") (pinfunction "OUT15_15") (pintype "output"))
      (node (ref "JP5") (pin "16") (pinfunction "P$16_16") (pintype "bidirectional"))
      (node (ref "LED48") (pin "C") (pinfunction "C_C") (pintype "passive"))
    )
    (net (code "72") (name "Net-(R3-Pad1)") (class "Default")
      (node (ref "R3") (pin "1") (pinfunction "1_1") (pintype "passive"))
      (node (ref "R4") (pin "2") (pinfunction "2_2") (pintype "passive"))
      (node (ref "R5") (pin "1") (pinfunction "1_1") (pintype "passive"))
    )
    (net (code "73") (name "Net-(SW1-P$2)") (class "Default")
      (node (ref "C5") (pin "1") (pinfunction "1_1") (pintype "passive"))
      (node (ref "D3") (pin "A") (pinfunction "A_A") (pintype "passive"))
      (node (ref "R2") (pin "2") (pinfunction "2_2") (pintype "passive"))
      (node (ref "R3") (pin "2") (pinfunction "2_2") (pintype "passive"))
      (node (ref "SW1") (pin "2") (pinfunction "P$2_2") (pintype "bidirectional"))
    )
    (net (code "74") (name "VCC") (class "Default")
      (node (ref "C4") (pin "1") (pinfunction "1_1") (pintype "passive"))
      (node (ref "C6") (pin "1") (pinfunction "+_1") (pintype "passive"))
      (node (ref "C7") (pin "1") (pinfunction "1_1") (pintype "passive"))
      (node (ref "C8") (pin "1") (pinfunction "1_1") (pintype "passive"))
      (node (ref "C9") (pin "1") (pinfunction "1_1") (pintype "passive"))
      (node (ref "IC1") (pin "7") (pinfunction "VCC_7") (pintype "power_in"))
      (node (ref "IC2") (pin "5") (pinfunction "OUT_5") (pintype "output"))
      (node (ref "IC3") (pin "21") (pinfunction "VCC_21") (pintype "power_in"))
      (node (ref "IC4") (pin "21") (pinfunction "VCC_21") (pintype "power_in"))
      (node (ref "IC5") (pin "21") (pinfunction "VCC_21") (pintype "power_in"))
      (node (ref "ISP1") (pin "VCC") (pinfunction "VCC_VCC") (pintype "power_in"))
      (node (ref "JP2") (pin "1") (pinfunction "1_1") (pintype "bidirectional"))
      (node (ref "JP6") (pin "1") (pinfunction "1_1") (pintype "bidirectional"))
      (node (ref "L1") (pin "2") (pinfunction "2_2") (pintype "passive"))
      (node (ref "LED1") (pin "A") (pinfunction "A_A") (pintype "passive"))
      (node (ref "LED10") (pin "A") (pinfunction "A_A") (pintype "passive"))
      (node (ref "LED11") (pin "A") (pinfunction "A_A") (pintype "passive"))
      (node (ref "LED12") (pin "A") (pinfunction "A_A") (pintype "passive"))
      (node (ref "LED13") (pin "A") (pinfunction "A_A") (pintype "passive"))
      (node (ref "LED14") (pin "A") (pinfunction "A_A") (pintype "passive"))
      (node (ref "LED15") (pin "A") (pinfunction "A_A") (pintype "passive"))
      (node (ref "LED16") (pin "A") (pinfunction "A_A") (pintype "passive"))
      (node (ref "LED17") (pin "A") (pinfunction "A_A") (pintype "passive"))
      (node (ref "LED18") (pin "A") (pinfunction "A_A") (pintype "passive"))
      (node (ref "LED19") (pin "A") (pinfunction "A_A") (pintype "passive"))
      (node (ref "LED2") (pin "A") (pinfunction "A_A") (pintype "passive"))
      (node (ref "LED20") (pin "A") (pinfunction "A_A") (pintype "passive"))
      (node (ref "LED21") (pin "A") (pinfunction "A_A") (pintype "passive"))
      (node (ref "LED22") (pin "A") (pinfunction "A_A") (pintype "passive"))
      (node (ref "LED23") (pin "A") (pinfunction "A_A") (pintype "passive"))
      (node (ref "LED24") (pin "A") (pinfunction "A_A") (pintype "passive"))
      (node (ref "LED25") (pin "A") (pinfunction "A_A") (pintype "passive"))
      (node (ref "LED26") (pin "A") (pinfunction "A_A") (pintype "passive"))
      (node (ref "LED27") (pin "A") (pinfunction "A_A") (pintype "passive"))
      (node (ref "LED28") (pin "A") (pinfunction "A_A") (pintype "passive"))
      (node (ref "LED29") (pin "A") (pinfunction "A_A") (pintype "passive"))
      (node (ref "LED3") (pin "A") (pinfunction "A_A") (pintype "passive"))
      (node (ref "LED30") (pin "A") (pinfunction "A_A") (pintype "passive"))
      (node (ref "LED31") (pin "A") (pinfunction "A_A") (pintype "passive"))
      (node (ref "LED32") (pin "A") (pinfunction "A_A") (pintype "passive"))
      (node (ref "LED33") (pin "A") (pinfunction "A_A") (pintype "passive"))
      (node (ref "LED34") (pin "A") (pinfunction "A_A") (pintype "passive"))
      (node (ref "LED35") (pin "A") (pinfunction "A_A") (pintype "passive"))
      (node (ref "LED36") (pin "A") (pinfunction "A_A") (pintype "passive"))
      (node (ref "LED37") (pin "A") (pinfunction "A_A") (pintype "passive"))
      (node (ref "LED38") (pin "A") (pinfunction "A_A") (pintype "passive"))
      (node (ref "LED39") (pin "A") (pinfunction "A_A") (pintype "passive"))
      (node (ref "LED4") (pin "A") (pinfunction "A_A") (pintype "passive"))
      (node (ref "LED40") (pin "A") (pinfunction "A_A") (pintype "passive"))
      (node (ref "LED41") (pin "A") (pinfunction "A_A") (pintype "passive"))
      (node (ref "LED42") (pin "A") (pinfunction "A_A") (pintype "passive"))
      (node (ref "LED43") (pin "A") (pinfunction "A_A") (pintype "passive"))
      (node (ref "LED44") (pin "A") (pinfunction "A_A") (pintype "passive"))
      (node (ref "LED45") (pin "A") (pinfunction "A_A") (pintype "passive"))
      (node (ref "LED46") (pin "A") (pinfunction "A_A") (pintype "passive"))
      (node (ref "LED47") (pin "A") (pinfunction "A_A") (pintype "passive"))
      (node (ref "LED48") (pin "A") (pinfunction "A_A") (pintype "passive"))
      (node (ref "LED5") (pin "A") (pinfunction "A_A") (pintype "passive"))
      (node (ref "LED6") (pin "A") (pinfunction "A_A") (pintype "passive"))
      (node (ref "LED7") (pin "A") (pinfunction "A_A") (pintype "passive"))
      (node (ref "LED8") (pin "A") (pinfunction "A_A") (pintype "passive"))
      (node (ref "LED9") (pin "A") (pinfunction "A_A") (pintype "passive"))
      (node (ref "R1") (pin "2") (pinfunction "2_2") (pintype "passive"))
      (node (ref "R6") (pin "2") (pinfunction "2_2") (pintype "passive"))
      (node (ref "R7") (pin "2") (pinfunction "2_2") (pintype "passive"))
      (node (ref "R8") (pin "2") (pinfunction "2_2") (pintype "passive"))
    )
    (net (code "75") (name "unconnected-(IC1-PC0(ADC0)-Pad23)") (class "Default")
      (node (ref "IC1") (pin "23") (pinfunction "PC0(ADC0)_23") (pintype "bidirectional"))
    )
    (net (code "76") (name "unconnected-(IC1-PC1(ADC1)-Pad24)") (class "Default")
      (node (ref "IC1") (pin "24") (pinfunction "PC1(ADC1)_24") (pintype "bidirectional"))
    )
    (net (code "77") (name "unconnected-(IC1-PC2(ADC2)-Pad25)") (class "Default")
      (node (ref "IC1") (pin "25") (pinfunction "PC2(ADC2)_25") (pintype "bidirectional"))
    )
    (net (code "78") (name "unconnected-(IC1-PC3(ADC3)-Pad26)") (class "Default")
      (node (ref "IC1") (pin "26") (pinfunction "PC3(ADC3)_26") (pintype "bidirectional"))
    )
    (net (code "79") (name "unconnected-(IC1-PC4(ADC4{slash}SDA)-Pad27)") (class "Default")
      (node (ref "IC1") (pin "27") (pinfunction "PC4(ADC4/SDA)_27") (pintype "bidirectional"))
    )
    (net (code "80") (name "unconnected-(IC1-PC5(ADC5{slash}SCL)-Pad28)") (class "Default")
      (node (ref "IC1") (pin "28") (pinfunction "PC5(ADC5/SCL)_28") (pintype "bidirectional"))
    )
    (net (code "81") (name "unconnected-(IC1-PD3(INT1)-Pad5)") (class "Default")
      (node (ref "IC1") (pin "5") (pinfunction "PD3(INT1)_5") (pintype "bidirectional"))
    )
    (net (code "82") (name "unconnected-(IC1-PD4(XCK{slash}T0)-Pad6)") (class "Default")
      (node (ref "IC1") (pin "6") (pinfunction "PD4(XCK/T0)_6") (pintype "bidirectional"))
    )
    (net (code "83") (name "unconnected-(IC1-PD5(T1)-Pad11)") (class "Default")
      (node (ref "IC1") (pin "11") (pinfunction "PD5(T1)_11") (pintype "bidirectional"))
    )
    (net (code "84") (name "unconnected-(IC1-PD6(AIN0)-Pad12)") (class "Default")
      (node (ref "IC1") (pin "12") (pinfunction "PD6(AIN0)_12") (pintype "bidirectional"))
    )
    (net (code "85") (name "unconnected-(IC2-ADJ-Pad4)") (class "Default")
      (node (ref "IC2") (pin "4") (pinfunction "ADJ_4") (pintype "passive"))
    )
    (net (code "86") (name "unconnected-(IC3-XERR-Pad16)") (class "Default")
      (node (ref "IC3") (pin "16") (pinfunction "XERR_16") (pintype "output"))
    )
    (net (code "87") (name "unconnected-(IC4-XERR-Pad16)") (class "Default")
      (node (ref "IC4") (pin "16") (pinfunction "XERR_16") (pintype "output"))
    )
    (net (code "88") (name "unconnected-(IC5-SOUT-Pad17)") (class "Default")
      (node (ref "IC5") (pin "17") (pinfunction "SOUT_17") (pintype "output"))
    )
    (net (code "89") (name "unconnected-(IC5-XERR-Pad16)") (class "Default")
      (node (ref "IC5") (pin "16") (pinfunction "XERR_16") (pintype "output"))
    )
    (net (code "90") (name "unconnected-(LED2-PadC)") (class "Default")
      (node (ref "LED2") (pin "C") (pinfunction "C_C") (pintype "passive"))
    )
    (net (code "91") (name "unconnected-(LED3-PadC)") (class "Default")
      (node (ref "LED3") (pin "C") (pinfunction "C_C") (pintype "passive"))
    )
    (net (code "92") (name "unconnected-(LED4-PadC)") (class "Default")
      (node (ref "LED4") (pin "C") (pinfunction "C_C") (pintype "passive"))
    )
    (net (code "93") (name "unconnected-(LED5-PadC)") (class "Default")
      (node (ref "LED5") (pin "C") (pinfunction "C_C") (pintype "passive"))
    )
    (net (code "94") (name "unconnected-(LED6-PadC)") (class "Default")
      (node (ref "LED6") (pin "C") (pinfunction "C_C") (pintype "passive"))
    )
    (net (code "95") (name "unconnected-(LED8-PadC)") (class "Default")
      (node (ref "LED8") (pin "C") (pinfunction "C_C") (pintype "passive"))
    )
    (net (code "96") (name "unconnected-(LED9-PadC)") (class "Default")
      (node (ref "LED9") (pin "C") (pinfunction "C_C") (pintype "passive"))
    )
    (net (code "97") (name "unconnected-(LED10-PadC)") (class "Default")
      (node (ref "LED10") (pin "C") (pinfunction "C_C") (pintype "passive"))
    )
    (net (code "98") (name "unconnected-(LED11-PadC)") (class "Default")
      (node (ref "LED11") (pin "C") (pinfunction "C_C") (pintype "passive"))
    )
    (net (code "99") (name "unconnected-(LED12-PadC)") (class "Default")
      (node (ref "LED12") (pin "C") (pinfunction "C_C") (pintype "passive"))
    )
    (net (code "100") (name "unconnected-(LED13-PadC)") (class "Default")
      (node (ref "LED13") (pin "C") (pinfunction "C_C") (pintype "passive"))
    )
    (net (code "101") (name "unconnected-(LED14-PadC)") (class "Default")
      (node (ref "LED14") (pin "C") (pinfunction "C_C") (pintype "passive"))
    )
    (net (code "102") (name "unconnected-(LED16-PadC)") (class "Default")
      (node (ref "LED16") (pin "C") (pinfunction "C_C") (pintype "passive"))
    )
  )
)
